# KBConvE7.net
KiCad netlist of a schematic drawn in EAGLE
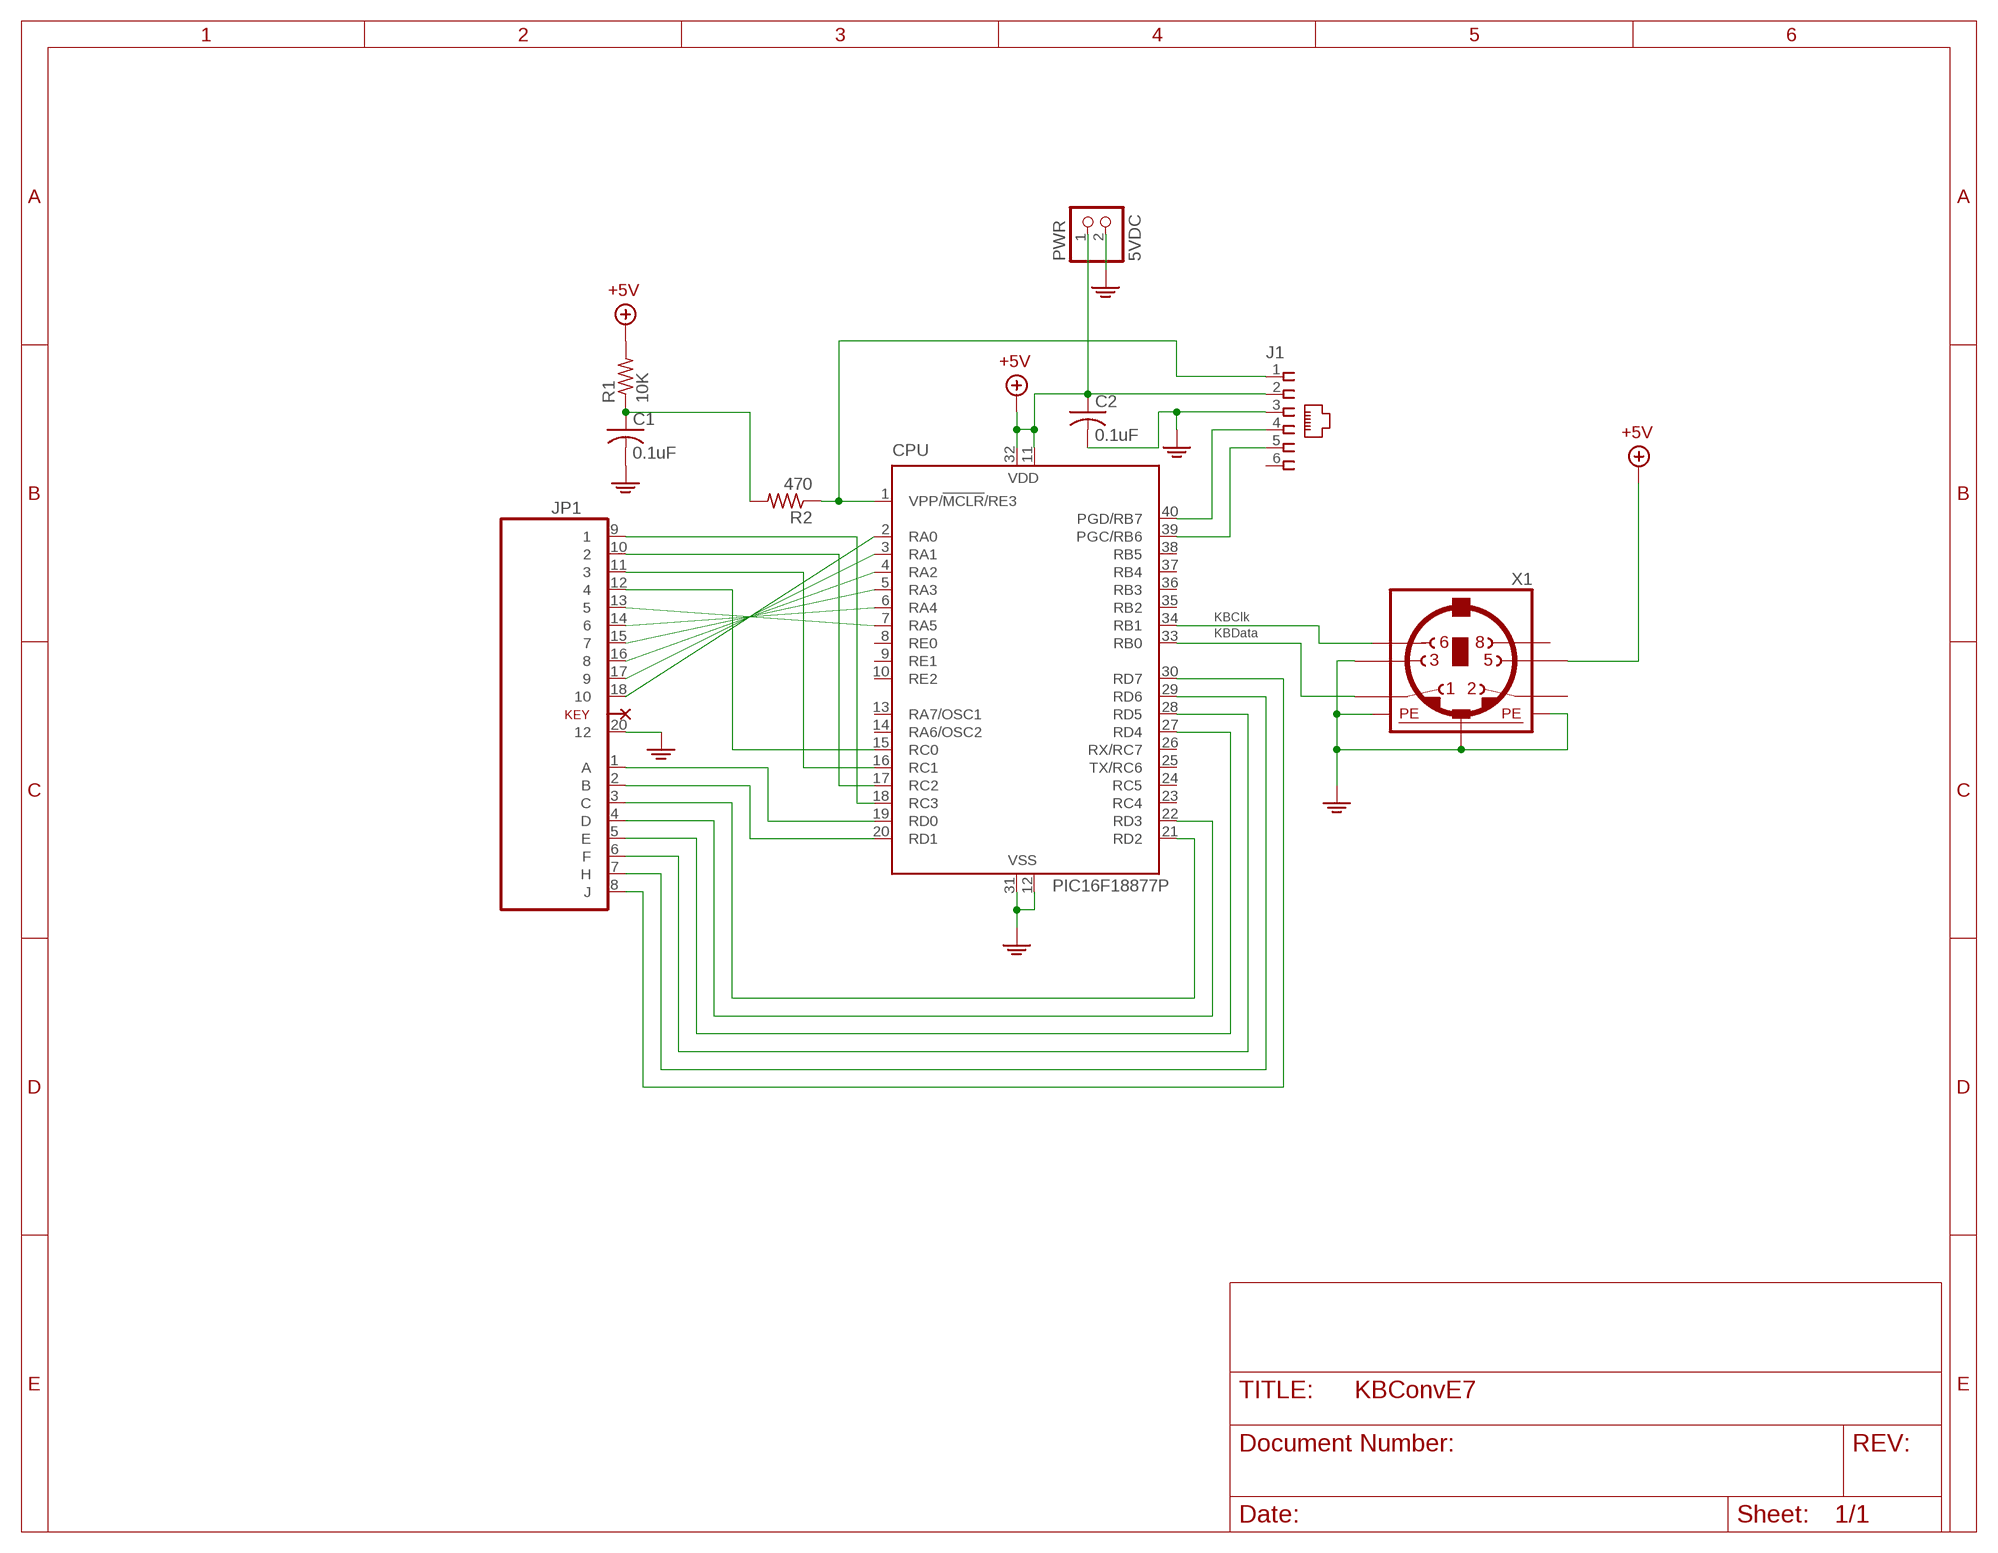
[diagram p0: schematic, sheet 1]

(export (version "E")
  (design (tool "Eeschema 10.0.6"))
  (components
    (comp (ref "C1")
      (value "0.1uF")
      (footprint "eagle-import:C025-025X050")
      (libsource (lib "eagle-import") (part "C-US025-025X050"))
    )
    (comp (ref "C2")
      (value "0.1uF")
      (footprint "eagle-import:C025-025X050")
      (libsource (lib "eagle-import") (part "C-US025-025X050"))
    )
    (comp (ref "CPU")
      (value "PIC16F18877P")
      (footprint "eagle-import:DIL40")
      (libsource (lib "eagle-import") (part "PIC16F18877P"))
    )
    (comp (ref "J1")
      (value "520250-3")
      (footprint "eagle-import:520250-3")
      (libsource (lib "eagle-import") (part "520250-3"))
    )
    (comp (ref "JP1")
      (value "PET_KEYBOARD")
      (footprint "eagle-import:PET_KEYBOARD")
      (libsource (lib "eagle-import") (part "PET_KEYBOARD"))
    )
    (comp (ref "PWR")
      (value "5VDC")
      (footprint "eagle-import:1X02")
      (libsource (lib "eagle-import") (part "PINHD-1X2"))
    )
    (comp (ref "R1")
      (value "10K")
      (footprint "eagle-import:0207_10")
      (libsource (lib "eagle-import") (part "R-US_0207/10"))
    )
    (comp (ref "R2")
      (value "470")
      (footprint "eagle-import:0207_10")
      (libsource (lib "eagle-import") (part "R-US_0207/10"))
    )
    (comp (ref "X1")
      (value "MINI_DIN_6")
      (footprint "eagle-import:M_DIN6")
      (libsource (lib "eagle-import") (part "MINI_DIN_6"))
    )
  )
  (nets
    (net (code "1") (name "+5V") (class "Default")
      (node (ref "C2") (pin "1") (pinfunction "1_1") (pintype "passive"))
      (node (ref "CPU") (pin "11") (pinfunction "VDD_11") (pintype "power_in"))
      (node (ref "CPU") (pin "32") (pinfunction "VDD_32") (pintype "power_in"))
      (node (ref "J1") (pin "2") (pinfunction "2_2") (pintype "passive"))
      (node (ref "PWR") (pin "1") (pinfunction "1_1") (pintype "passive"))
      (node (ref "R1") (pin "2") (pinfunction "2_2") (pintype "passive"))
      (node (ref "X1") (pin "5") (pinfunction "5_5") (pintype "passive"))
    )
    (net (code "2") (name "GND") (class "Default")
      (node (ref "C1") (pin "2") (pinfunction "2_2") (pintype "passive"))
      (node (ref "C2") (pin "2") (pinfunction "2_2") (pintype "passive"))
      (node (ref "CPU") (pin "12") (pinfunction "VSS_12") (pintype "power_in"))
      (node (ref "CPU") (pin "31") (pinfunction "VSS_31") (pintype "power_in"))
      (node (ref "J1") (pin "3") (pinfunction "3_3") (pintype "passive"))
      (node (ref "JP1") (pin "20") (pinfunction "12_20") (pintype "passive"))
      (node (ref "PWR") (pin "2") (pinfunction "2_2") (pintype "passive"))
      (node (ref "X1") (pin "3") (pinfunction "3_3") (pintype "passive"))
      (node (ref "X1") (pin "SH1") (pinfunction "PE1_SH1") (pintype "power_in"))
      (node (ref "X1") (pin "SH2") (pinfunction "PE2_SH2") (pintype "power_in"))
      (node (ref "X1") (pin "SH3") (pinfunction "PE3_SH3") (pintype "power_in"))
    )
    (net (code "3") (name "Net-(C1-Pad1)") (class "Default")
      (node (ref "C1") (pin "1") (pinfunction "1_1") (pintype "passive"))
      (node (ref "R1") (pin "1") (pinfunction "1_1") (pintype "passive"))
      (node (ref "R2") (pin "2") (pinfunction "2_2") (pintype "passive"))
    )
    (net (code "4") (name "Net-(CPU-PGC{slash}RB6)") (class "Default")
      (node (ref "CPU") (pin "39") (pinfunction "PGC/RB6_39") (pintype "bidirectional"))
      (node (ref "J1") (pin "5") (pinfunction "5_5") (pintype "passive"))
    )
    (net (code "5") (name "Net-(CPU-PGD{slash}RB7)") (class "Default")
      (node (ref "CPU") (pin "40") (pinfunction "PGD/RB7_40") (pintype "bidirectional"))
      (node (ref "J1") (pin "4") (pinfunction "4_4") (pintype "passive"))
    )
    (net (code "6") (name "Net-(CPU-RA0)") (class "Default")
      (node (ref "CPU") (pin "2") (pinfunction "RA0_2") (pintype "bidirectional"))
      (node (ref "JP1") (pin "18") (pinfunction "10_18") (pintype "passive"))
    )
    (net (code "7") (name "Net-(CPU-RA1)") (class "Default")
      (node (ref "CPU") (pin "3") (pinfunction "RA1_3") (pintype "bidirectional"))
      (node (ref "JP1") (pin "17") (pinfunction "9_17") (pintype "passive"))
    )
    (net (code "8") (name "Net-(CPU-RA2)") (class "Default")
      (node (ref "CPU") (pin "4") (pinfunction "RA2_4") (pintype "bidirectional"))
      (node (ref "JP1") (pin "16") (pinfunction "8_16") (pintype "passive"))
    )
    (net (code "9") (name "Net-(CPU-RA3)") (class "Default")
      (node (ref "CPU") (pin "5") (pinfunction "RA3_5") (pintype "bidirectional"))
      (node (ref "JP1") (pin "15") (pinfunction "7_15") (pintype "passive"))
    )
    (net (code "10") (name "Net-(CPU-RA4)") (class "Default")
      (node (ref "CPU") (pin "6") (pinfunction "RA4_6") (pintype "bidirectional"))
      (node (ref "JP1") (pin "14") (pinfunction "6_14") (pintype "passive"))
    )
    (net (code "11") (name "Net-(CPU-RA5)") (class "Default")
      (node (ref "CPU") (pin "7") (pinfunction "RA5_7") (pintype "bidirectional"))
      (node (ref "JP1") (pin "13") (pinfunction "5_13") (pintype "passive"))
    )
    (net (code "12") (name "Net-(CPU-RB0)") (class "Default")
      (node (ref "CPU") (pin "33") (pinfunction "RB0_33") (pintype "bidirectional"))
      (node (ref "X1") (pin "1") (pinfunction "1_1") (pintype "passive"))
    )
    (net (code "13") (name "Net-(CPU-RB1)") (class "Default")
      (node (ref "CPU") (pin "34") (pinfunction "RB1_34") (pintype "bidirectional"))
      (node (ref "X1") (pin "6") (pinfunction "6_6") (pintype "passive"))
    )
    (net (code "14") (name "Net-(CPU-RC0)") (class "Default")
      (node (ref "CPU") (pin "15") (pinfunction "RC0_15") (pintype "bidirectional"))
      (node (ref "JP1") (pin "12") (pinfunction "4_12") (pintype "passive"))
    )
    (net (code "15") (name "Net-(CPU-RC1)") (class "Default")
      (node (ref "CPU") (pin "16") (pinfunction "RC1_16") (pintype "bidirectional"))
      (node (ref "JP1") (pin "11") (pinfunction "3_11") (pintype "passive"))
    )
    (net (code "16") (name "Net-(CPU-RC2)") (class "Default")
      (node (ref "CPU") (pin "17") (pinfunction "RC2_17") (pintype "bidirectional"))
      (node (ref "JP1") (pin "10") (pinfunction "2_10") (pintype "passive"))
    )
    (net (code "17") (name "Net-(CPU-RC3)") (class "Default")
      (node (ref "CPU") (pin "18") (pinfunction "RC3_18") (pintype "bidirectional"))
      (node (ref "JP1") (pin "9") (pinfunction "1_9") (pintype "passive"))
    )
    (net (code "18") (name "Net-(CPU-RD0)") (class "Default")
      (node (ref "CPU") (pin "19") (pinfunction "RD0_19") (pintype "bidirectional"))
      (node (ref "JP1") (pin "1") (pinfunction "A_1") (pintype "passive"))
    )
    (net (code "19") (name "Net-(CPU-RD1)") (class "Default")
      (node (ref "CPU") (pin "20") (pinfunction "RD1_20") (pintype "bidirectional"))
      (node (ref "JP1") (pin "2") (pinfunction "B_2") (pintype "passive"))
    )
    (net (code "20") (name "Net-(CPU-RD2)") (class "Default")
      (node (ref "CPU") (pin "21") (pinfunction "RD2_21") (pintype "bidirectional"))
      (node (ref "JP1") (pin "3") (pinfunction "C_3") (pintype "passive"))
    )
    (net (code "21") (name "Net-(CPU-RD3)") (class "Default")
      (node (ref "CPU") (pin "22") (pinfunction "RD3_22") (pintype "bidirectional"))
      (node (ref "JP1") (pin "4") (pinfunction "D_4") (pintype "passive"))
    )
    (net (code "22") (name "Net-(CPU-RD4)") (class "Default")
      (node (ref "CPU") (pin "27") (pinfunction "RD4_27") (pintype "bidirectional"))
      (node (ref "JP1") (pin "5") (pinfunction "E_5") (pintype "passive"))
    )
    (net (code "23") (name "Net-(CPU-RD5)") (class "Default")
      (node (ref "CPU") (pin "28") (pinfunction "RD5_28") (pintype "bidirectional"))
      (node (ref "JP1") (pin "6") (pinfunction "F_6") (pintype "passive"))
    )
    (net (code "24") (name "Net-(CPU-RD6)") (class "Default")
      (node (ref "CPU") (pin "29") (pinfunction "RD6_29") (pintype "bidirectional"))
      (node (ref "JP1") (pin "7") (pinfunction "H_7") (pintype "passive"))
    )
    (net (code "25") (name "Net-(CPU-RD7)") (class "Default")
      (node (ref "CPU") (pin "30") (pinfunction "RD7_30") (pintype "bidirectional"))
      (node (ref "JP1") (pin "8") (pinfunction "J_8") (pintype "passive"))
    )
    (net (code "26") (name "Net-(CPU-VPP{slash}~{MCLR}{slash}RE3)") (class "Default")
      (node (ref "CPU") (pin "1") (pinfunction "VPP/~{MCLR}/RE3_1") (pintype "input"))
      (node (ref "J1") (pin "1") (pinfunction "1_1") (pintype "passive"))
      (node (ref "R2") (pin "1") (pinfunction "1_1") (pintype "passive"))
    )
    (net (code "27") (name "unconnected-(CPU-RA6{slash}OSC2-Pad14)") (class "Default")
      (node (ref "CPU") (pin "14") (pinfunction "RA6/OSC2_14") (pintype "output"))
    )
    (net (code "28") (name "unconnected-(CPU-RA7{slash}OSC1-Pad13)") (class "Default")
      (node (ref "CPU") (pin "13") (pinfunction "RA7/OSC1_13") (pintype "input"))
    )
    (net (code "29") (name "unconnected-(CPU-RB2-Pad35)") (class "Default")
      (node (ref "CPU") (pin "35") (pinfunction "RB2_35") (pintype "bidirectional"))
    )
    (net (code "30") (name "unconnected-(CPU-RB3-Pad36)") (class "Default")
      (node (ref "CPU") (pin "36") (pinfunction "RB3_36") (pintype "bidirectional"))
    )
    (net (code "31") (name "unconnected-(CPU-RB4-Pad37)") (class "Default")
      (node (ref "CPU") (pin "37") (pinfunction "RB4_37") (pintype "bidirectional"))
    )
    (net (code "32") (name "unconnected-(CPU-RB5-Pad38)") (class "Default")
      (node (ref "CPU") (pin "38") (pinfunction "RB5_38") (pintype "bidirectional"))
    )
    (net (code "33") (name "unconnected-(CPU-RC4-Pad23)") (class "Default")
      (node (ref "CPU") (pin "23") (pinfunction "RC4_23") (pintype "bidirectional"))
    )
    (net (code "34") (name "unconnected-(CPU-RC5-Pad24)") (class "Default")
      (node (ref "CPU") (pin "24") (pinfunction "RC5_24") (pintype "bidirectional"))
    )
    (net (code "35") (name "unconnected-(CPU-RE0-Pad8)") (class "Default")
      (node (ref "CPU") (pin "8") (pinfunction "RE0_8") (pintype "bidirectional"))
    )
    (net (code "36") (name "unconnected-(CPU-RE1-Pad9)") (class "Default")
      (node (ref "CPU") (pin "9") (pinfunction "RE1_9") (pintype "bidirectional"))
    )
    (net (code "37") (name "unconnected-(CPU-RE2-Pad10)") (class "Default")
      (node (ref "CPU") (pin "10") (pinfunction "RE2_10") (pintype "bidirectional"))
    )
    (net (code "38") (name "unconnected-(CPU-RX{slash}RC7-Pad26)") (class "Default")
      (node (ref "CPU") (pin "26") (pinfunction "RX/RC7_26") (pintype "bidirectional"))
    )
    (net (code "39") (name "unconnected-(CPU-TX{slash}RC6-Pad25)") (class "Default")
      (node (ref "CPU") (pin "25") (pinfunction "TX/RC6_25") (pintype "bidirectional"))
    )
    (net (code "40") (name "unconnected-(J1-Pad6)") (class "Default")
      (node (ref "J1") (pin "6") (pinfunction "6_6") (pintype "passive"))
    )
    (net (code "41") (name "unconnected-(X1-Pad2)") (class "Default")
      (node (ref "X1") (pin "2") (pinfunction "2_2") (pintype "passive"))
    )
    (net (code "42") (name "unconnected-(X1-Pad8)") (class "Default")
      (node (ref "X1") (pin "8") (pinfunction "8_8") (pintype "passive"))
    )
  )
)
